# MIA_Array.net
KiCad netlist of a schematic drawn in EAGLE
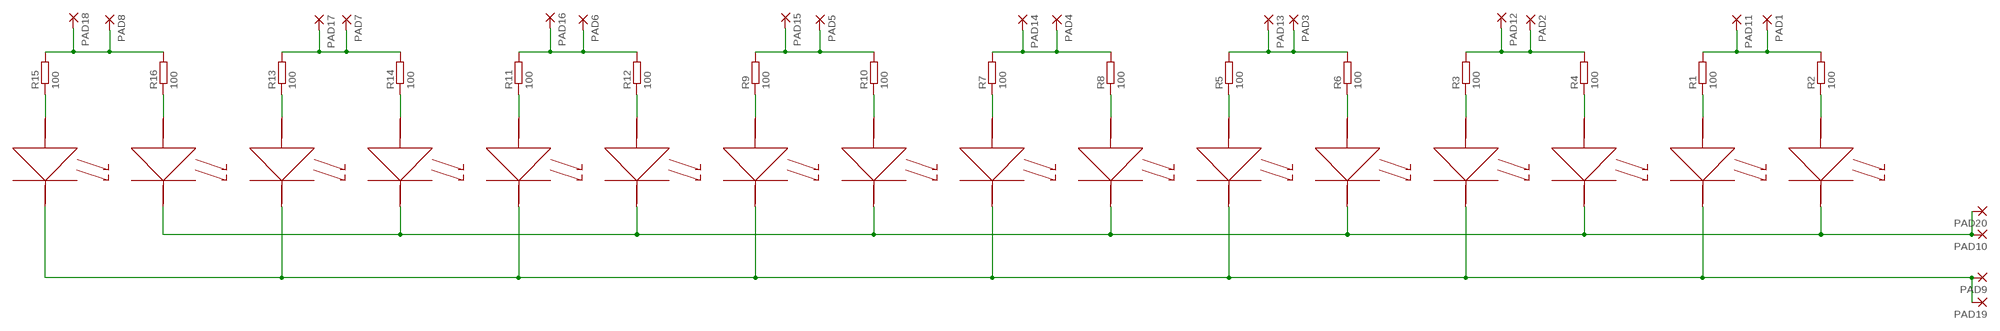
[diagram p0: schematic, sheet 1]

(export (version "E")
  (design (tool "Eeschema 10.0.6"))
  (components
    (comp (ref "PAD1")
      (value "2,54/1,1")
      (footprint "eagle-import:2,54_1,1")
      (libsource (lib "eagle-import") (part "2,54/1,1"))
    )
    (comp (ref "PAD2")
      (value "2,54/1,1")
      (footprint "eagle-import:2,54_1,1")
      (libsource (lib "eagle-import") (part "2,54/1,1"))
    )
    (comp (ref "PAD3")
      (value "2,54/1,1")
      (footprint "eagle-import:2,54_1,1")
      (libsource (lib "eagle-import") (part "2,54/1,1"))
    )
    (comp (ref "PAD4")
      (value "2,54/1,1")
      (footprint "eagle-import:2,54_1,1")
      (libsource (lib "eagle-import") (part "2,54/1,1"))
    )
    (comp (ref "PAD5")
      (value "2,54/1,1")
      (footprint "eagle-import:2,54_1,1")
      (libsource (lib "eagle-import") (part "2,54/1,1"))
    )
    (comp (ref "PAD6")
      (value "2,54/1,1")
      (footprint "eagle-import:2,54_1,1")
      (libsource (lib "eagle-import") (part "2,54/1,1"))
    )
    (comp (ref "PAD7")
      (value "2,54/1,1")
      (footprint "eagle-import:2,54_1,1")
      (libsource (lib "eagle-import") (part "2,54/1,1"))
    )
    (comp (ref "PAD8")
      (value "2,54/1,1")
      (footprint "eagle-import:2,54_1,1")
      (libsource (lib "eagle-import") (part "2,54/1,1"))
    )
    (comp (ref "PAD9")
      (value "2,54/1,1")
      (footprint "eagle-import:2,54_1,1")
      (libsource (lib "eagle-import") (part "2,54/1,1"))
    )
    (comp (ref "PAD10")
      (value "2,54/1,1")
      (footprint "eagle-import:2,54_1,1")
      (libsource (lib "eagle-import") (part "2,54/1,1"))
    )
    (comp (ref "PAD11")
      (value "2,54/1,1")
      (footprint "eagle-import:2,54_1,1")
      (libsource (lib "eagle-import") (part "2,54/1,1"))
    )
    (comp (ref "PAD12")
      (value "2,54/1,1")
      (footprint "eagle-import:2,54_1,1")
      (libsource (lib "eagle-import") (part "2,54/1,1"))
    )
    (comp (ref "PAD13")
      (value "2,54/1,1")
      (footprint "eagle-import:2,54_1,1")
      (libsource (lib "eagle-import") (part "2,54/1,1"))
    )
    (comp (ref "PAD14")
      (value "2,54/1,1")
      (footprint "eagle-import:2,54_1,1")
      (libsource (lib "eagle-import") (part "2,54/1,1"))
    )
    (comp (ref "PAD15")
      (value "2,54/1,1")
      (footprint "eagle-import:2,54_1,1")
      (libsource (lib "eagle-import") (part "2,54/1,1"))
    )
    (comp (ref "PAD16")
      (value "2,54/1,1")
      (footprint "eagle-import:2,54_1,1")
      (libsource (lib "eagle-import") (part "2,54/1,1"))
    )
    (comp (ref "PAD17")
      (value "2,54/1,1")
      (footprint "eagle-import:2,54_1,1")
      (libsource (lib "eagle-import") (part "2,54/1,1"))
    )
    (comp (ref "PAD18")
      (value "2,54/1,1")
      (footprint "eagle-import:2,54_1,1")
      (libsource (lib "eagle-import") (part "2,54/1,1"))
    )
    (comp (ref "PAD19")
      (value "2,54/1,1")
      (footprint "eagle-import:2,54_1,1")
      (libsource (lib "eagle-import") (part "2,54/1,1"))
    )
    (comp (ref "PAD20")
      (value "2,54/1,1")
      (footprint "eagle-import:2,54_1,1")
      (libsource (lib "eagle-import") (part "2,54/1,1"))
    )
    (comp (ref "R1")
      (value "100")
      (footprint "eagle-import:0411_15")
      (libsource (lib "eagle-import") (part "R-EU_0411/15"))
    )
    (comp (ref "R2")
      (value "100")
      (footprint "eagle-import:0411_15")
      (libsource (lib "eagle-import") (part "R-EU_0411/15"))
    )
    (comp (ref "R3")
      (value "100")
      (footprint "eagle-import:0411_15")
      (libsource (lib "eagle-import") (part "R-EU_0411/15"))
    )
    (comp (ref "R4")
      (value "100")
      (footprint "eagle-import:0411_15")
      (libsource (lib "eagle-import") (part "R-EU_0411/15"))
    )
    (comp (ref "R5")
      (value "100")
      (footprint "eagle-import:0411_15")
      (libsource (lib "eagle-import") (part "R-EU_0411/15"))
    )
    (comp (ref "R6")
      (value "100")
      (footprint "eagle-import:0411_15")
      (libsource (lib "eagle-import") (part "R-EU_0411/15"))
    )
    (comp (ref "R7")
      (value "100")
      (footprint "eagle-import:0411_15")
      (libsource (lib "eagle-import") (part "R-EU_0411/15"))
    )
    (comp (ref "R8")
      (value "100")
      (footprint "eagle-import:0411_15")
      (libsource (lib "eagle-import") (part "R-EU_0411/15"))
    )
    (comp (ref "R9")
      (value "100")
      (footprint "eagle-import:0411_15")
      (libsource (lib "eagle-import") (part "R-EU_0411/15"))
    )
    (comp (ref "R10")
      (value "100")
      (footprint "eagle-import:0411_15")
      (libsource (lib "eagle-import") (part "R-EU_0411/15"))
    )
    (comp (ref "R11")
      (value "100")
      (footprint "eagle-import:0411_15")
      (libsource (lib "eagle-import") (part "R-EU_0411/15"))
    )
    (comp (ref "R12")
      (value "100")
      (footprint "eagle-import:0411_15")
      (libsource (lib "eagle-import") (part "R-EU_0411/15"))
    )
    (comp (ref "R13")
      (value "100")
      (footprint "eagle-import:0411_15")
      (libsource (lib "eagle-import") (part "R-EU_0411/15"))
    )
    (comp (ref "R14")
      (value "100")
      (footprint "eagle-import:0411_15")
      (libsource (lib "eagle-import") (part "R-EU_0411/15"))
    )
    (comp (ref "R15")
      (value "100")
      (footprint "eagle-import:0411_15")
      (libsource (lib "eagle-import") (part "R-EU_0411/15"))
    )
    (comp (ref "R16")
      (value "100")
      (footprint "eagle-import:0411_15")
      (libsource (lib "eagle-import") (part "R-EU_0411/15"))
    )
    (comp (ref "U$1")
      (value "L150-3080502400000")
      (footprint "eagle-import:SMD-5050")
      (libsource (lib "eagle-import") (part "L150-3080502400000"))
    )
    (comp (ref "U$2")
      (value "L150-3080502400000")
      (footprint "eagle-import:SMD-5050")
      (libsource (lib "eagle-import") (part "L150-3080502400000"))
    )
    (comp (ref "U$3")
      (value "L150-3080502400000")
      (footprint "eagle-import:SMD-5050")
      (libsource (lib "eagle-import") (part "L150-3080502400000"))
    )
    (comp (ref "U$4")
      (value "L150-3080502400000")
      (footprint "eagle-import:SMD-5050")
      (libsource (lib "eagle-import") (part "L150-3080502400000"))
    )
    (comp (ref "U$5")
      (value "L150-3080502400000")
      (footprint "eagle-import:SMD-5050")
      (libsource (lib "eagle-import") (part "L150-3080502400000"))
    )
    (comp (ref "U$6")
      (value "L150-3080502400000")
      (footprint "eagle-import:SMD-5050")
      (libsource (lib "eagle-import") (part "L150-3080502400000"))
    )
    (comp (ref "U$7")
      (value "L150-3080502400000")
      (footprint "eagle-import:SMD-5050")
      (libsource (lib "eagle-import") (part "L150-3080502400000"))
    )
    (comp (ref "U$8")
      (value "L150-3080502400000")
      (footprint "eagle-import:SMD-5050")
      (libsource (lib "eagle-import") (part "L150-3080502400000"))
    )
    (comp (ref "U$9")
      (value "L150-3080502400000")
      (footprint "eagle-import:SMD-5050")
      (libsource (lib "eagle-import") (part "L150-3080502400000"))
    )
    (comp (ref "U$10")
      (value "L150-3080502400000")
      (footprint "eagle-import:SMD-5050")
      (libsource (lib "eagle-import") (part "L150-3080502400000"))
    )
    (comp (ref "U$11")
      (value "L150-3080502400000")
      (footprint "eagle-import:SMD-5050")
      (libsource (lib "eagle-import") (part "L150-3080502400000"))
    )
    (comp (ref "U$12")
      (value "L150-3080502400000")
      (footprint "eagle-import:SMD-5050")
      (libsource (lib "eagle-import") (part "L150-3080502400000"))
    )
    (comp (ref "U$13")
      (value "L150-3080502400000")
      (footprint "eagle-import:SMD-5050")
      (libsource (lib "eagle-import") (part "L150-3080502400000"))
    )
    (comp (ref "U$14")
      (value "L150-3080502400000")
      (footprint "eagle-import:SMD-5050")
      (libsource (lib "eagle-import") (part "L150-3080502400000"))
    )
    (comp (ref "U$15")
      (value "L150-3080502400000")
      (footprint "eagle-import:SMD-5050")
      (libsource (lib "eagle-import") (part "L150-3080502400000"))
    )
    (comp (ref "U$16")
      (value "L150-3080502400000")
      (footprint "eagle-import:SMD-5050")
      (libsource (lib "eagle-import") (part "L150-3080502400000"))
    )
  )
  (nets
    (net (code "1") (name "Net-(PAD1-P)") (class "Default")
      (node (ref "PAD1") (pin "1") (pinfunction "P_1") (pintype "passive"))
      (node (ref "PAD11") (pin "1") (pinfunction "P_1") (pintype "passive"))
      (node (ref "R1") (pin "2") (pinfunction "2_2") (pintype "passive"))
      (node (ref "R2") (pin "2") (pinfunction "2_2") (pintype "passive"))
    )
    (net (code "2") (name "Net-(PAD10-P)") (class "Default")
      (node (ref "PAD10") (pin "1") (pinfunction "P_1") (pintype "passive"))
      (node (ref "PAD20") (pin "1") (pinfunction "P_1") (pintype "passive"))
      (node (ref "U$11") (pin "CA") (pinfunction "CA_CA") (pintype "bidirectional"))
      (node (ref "U$11") (pin "CA2") (pinfunction "CA_CA2") (pintype "bidirectional"))
      (node (ref "U$12") (pin "CA") (pinfunction "CA_CA") (pintype "bidirectional"))
      (node (ref "U$12") (pin "CA2") (pinfunction "CA_CA2") (pintype "bidirectional"))
      (node (ref "U$14") (pin "CA") (pinfunction "CA_CA") (pintype "bidirectional"))
      (node (ref "U$14") (pin "CA2") (pinfunction "CA_CA2") (pintype "bidirectional"))
      (node (ref "U$16") (pin "CA") (pinfunction "CA_CA") (pintype "bidirectional"))
      (node (ref "U$16") (pin "CA2") (pinfunction "CA_CA2") (pintype "bidirectional"))
      (node (ref "U$2") (pin "CA") (pinfunction "CA_CA") (pintype "bidirectional"))
      (node (ref "U$2") (pin "CA2") (pinfunction "CA_CA2") (pintype "bidirectional"))
      (node (ref "U$5") (pin "CA") (pinfunction "CA_CA") (pintype "bidirectional"))
      (node (ref "U$5") (pin "CA2") (pinfunction "CA_CA2") (pintype "bidirectional"))
      (node (ref "U$7") (pin "CA") (pinfunction "CA_CA") (pintype "bidirectional"))
      (node (ref "U$7") (pin "CA2") (pinfunction "CA_CA2") (pintype "bidirectional"))
      (node (ref "U$9") (pin "CA") (pinfunction "CA_CA") (pintype "bidirectional"))
      (node (ref "U$9") (pin "CA2") (pinfunction "CA_CA2") (pintype "bidirectional"))
    )
    (net (code "3") (name "Net-(PAD12-P)") (class "Default")
      (node (ref "PAD12") (pin "1") (pinfunction "P_1") (pintype "passive"))
      (node (ref "PAD2") (pin "1") (pinfunction "P_1") (pintype "passive"))
      (node (ref "R3") (pin "2") (pinfunction "2_2") (pintype "passive"))
      (node (ref "R4") (pin "2") (pinfunction "2_2") (pintype "passive"))
    )
    (net (code "4") (name "Net-(PAD13-P)") (class "Default")
      (node (ref "PAD13") (pin "1") (pinfunction "P_1") (pintype "passive"))
      (node (ref "PAD3") (pin "1") (pinfunction "P_1") (pintype "passive"))
      (node (ref "R5") (pin "2") (pinfunction "2_2") (pintype "passive"))
      (node (ref "R6") (pin "2") (pinfunction "2_2") (pintype "passive"))
    )
    (net (code "5") (name "Net-(PAD14-P)") (class "Default")
      (node (ref "PAD14") (pin "1") (pinfunction "P_1") (pintype "passive"))
      (node (ref "PAD4") (pin "1") (pinfunction "P_1") (pintype "passive"))
      (node (ref "R7") (pin "2") (pinfunction "2_2") (pintype "passive"))
      (node (ref "R8") (pin "2") (pinfunction "2_2") (pintype "passive"))
    )
    (net (code "6") (name "Net-(PAD15-P)") (class "Default")
      (node (ref "PAD15") (pin "1") (pinfunction "P_1") (pintype "passive"))
      (node (ref "PAD5") (pin "1") (pinfunction "P_1") (pintype "passive"))
      (node (ref "R10") (pin "2") (pinfunction "2_2") (pintype "passive"))
      (node (ref "R9") (pin "2") (pinfunction "2_2") (pintype "passive"))
    )
    (net (code "7") (name "Net-(PAD16-P)") (class "Default")
      (node (ref "PAD16") (pin "1") (pinfunction "P_1") (pintype "passive"))
      (node (ref "PAD6") (pin "1") (pinfunction "P_1") (pintype "passive"))
      (node (ref "R11") (pin "2") (pinfunction "2_2") (pintype "passive"))
      (node (ref "R12") (pin "2") (pinfunction "2_2") (pintype "passive"))
    )
    (net (code "8") (name "Net-(PAD17-P)") (class "Default")
      (node (ref "PAD17") (pin "1") (pinfunction "P_1") (pintype "passive"))
      (node (ref "PAD7") (pin "1") (pinfunction "P_1") (pintype "passive"))
      (node (ref "R13") (pin "2") (pinfunction "2_2") (pintype "passive"))
      (node (ref "R14") (pin "2") (pinfunction "2_2") (pintype "passive"))
    )
    (net (code "9") (name "Net-(PAD18-P)") (class "Default")
      (node (ref "PAD18") (pin "1") (pinfunction "P_1") (pintype "passive"))
      (node (ref "PAD8") (pin "1") (pinfunction "P_1") (pintype "passive"))
      (node (ref "R15") (pin "2") (pinfunction "2_2") (pintype "passive"))
      (node (ref "R16") (pin "2") (pinfunction "2_2") (pintype "passive"))
    )
    (net (code "10") (name "Net-(PAD19-P)") (class "Default")
      (node (ref "PAD19") (pin "1") (pinfunction "P_1") (pintype "passive"))
      (node (ref "PAD9") (pin "1") (pinfunction "P_1") (pintype "passive"))
      (node (ref "U$1") (pin "CA") (pinfunction "CA_CA") (pintype "bidirectional"))
      (node (ref "U$1") (pin "CA2") (pinfunction "CA_CA2") (pintype "bidirectional"))
      (node (ref "U$10") (pin "CA") (pinfunction "CA_CA") (pintype "bidirectional"))
      (node (ref "U$10") (pin "CA2") (pinfunction "CA_CA2") (pintype "bidirectional"))
      (node (ref "U$13") (pin "CA") (pinfunction "CA_CA") (pintype "bidirectional"))
      (node (ref "U$13") (pin "CA2") (pinfunction "CA_CA2") (pintype "bidirectional"))
      (node (ref "U$15") (pin "CA") (pinfunction "CA_CA") (pintype "bidirectional"))
      (node (ref "U$15") (pin "CA2") (pinfunction "CA_CA2") (pintype "bidirectional"))
      (node (ref "U$3") (pin "CA") (pinfunction "CA_CA") (pintype "bidirectional"))
      (node (ref "U$3") (pin "CA2") (pinfunction "CA_CA2") (pintype "bidirectional"))
      (node (ref "U$4") (pin "CA") (pinfunction "CA_CA") (pintype "bidirectional"))
      (node (ref "U$4") (pin "CA2") (pinfunction "CA_CA2") (pintype "bidirectional"))
      (node (ref "U$6") (pin "CA") (pinfunction "CA_CA") (pintype "bidirectional"))
      (node (ref "U$6") (pin "CA2") (pinfunction "CA_CA2") (pintype "bidirectional"))
      (node (ref "U$8") (pin "CA") (pinfunction "CA_CA") (pintype "bidirectional"))
      (node (ref "U$8") (pin "CA2") (pinfunction "CA_CA2") (pintype "bidirectional"))
    )
    (net (code "11") (name "Net-(R1-Pad1)") (class "Default")
      (node (ref "R1") (pin "1") (pinfunction "1_1") (pintype "passive"))
      (node (ref "U$4") (pin "AN") (pinfunction "AN_AN") (pintype "bidirectional"))
      (node (ref "U$4") (pin "AN2") (pinfunction "AN_AN2") (pintype "bidirectional"))
    )
    (net (code "12") (name "Net-(R2-Pad1)") (class "Default")
      (node (ref "R2") (pin "1") (pinfunction "1_1") (pintype "passive"))
      (node (ref "U$12") (pin "AN") (pinfunction "AN_AN") (pintype "bidirectional"))
      (node (ref "U$12") (pin "AN2") (pinfunction "AN_AN2") (pintype "bidirectional"))
    )
    (net (code "13") (name "Net-(R3-Pad1)") (class "Default")
      (node (ref "R3") (pin "1") (pinfunction "1_1") (pintype "passive"))
      (node (ref "U$1") (pin "AN") (pinfunction "AN_AN") (pintype "bidirectional"))
      (node (ref "U$1") (pin "AN2") (pinfunction "AN_AN2") (pintype "bidirectional"))
    )
    (net (code "14") (name "Net-(R4-Pad1)") (class "Default")
      (node (ref "R4") (pin "1") (pinfunction "1_1") (pintype "passive"))
      (node (ref "U$2") (pin "AN") (pinfunction "AN_AN") (pintype "bidirectional"))
      (node (ref "U$2") (pin "AN2") (pinfunction "AN_AN2") (pintype "bidirectional"))
    )
    (net (code "15") (name "Net-(R5-Pad1)") (class "Default")
      (node (ref "R5") (pin "1") (pinfunction "1_1") (pintype "passive"))
      (node (ref "U$3") (pin "AN") (pinfunction "AN_AN") (pintype "bidirectional"))
      (node (ref "U$3") (pin "AN2") (pinfunction "AN_AN2") (pintype "bidirectional"))
    )
    (net (code "16") (name "Net-(R6-Pad1)") (class "Default")
      (node (ref "R6") (pin "1") (pinfunction "1_1") (pintype "passive"))
      (node (ref "U$5") (pin "AN") (pinfunction "AN_AN") (pintype "bidirectional"))
      (node (ref "U$5") (pin "AN2") (pinfunction "AN_AN2") (pintype "bidirectional"))
    )
    (net (code "17") (name "Net-(R7-Pad1)") (class "Default")
      (node (ref "R7") (pin "1") (pinfunction "1_1") (pintype "passive"))
      (node (ref "U$6") (pin "AN") (pinfunction "AN_AN") (pintype "bidirectional"))
      (node (ref "U$6") (pin "AN2") (pinfunction "AN_AN2") (pintype "bidirectional"))
    )
    (net (code "18") (name "Net-(R8-Pad1)") (class "Default")
      (node (ref "R8") (pin "1") (pinfunction "1_1") (pintype "passive"))
      (node (ref "U$7") (pin "AN") (pinfunction "AN_AN") (pintype "bidirectional"))
      (node (ref "U$7") (pin "AN2") (pinfunction "AN_AN2") (pintype "bidirectional"))
    )
    (net (code "19") (name "Net-(R9-Pad1)") (class "Default")
      (node (ref "R9") (pin "1") (pinfunction "1_1") (pintype "passive"))
      (node (ref "U$8") (pin "AN") (pinfunction "AN_AN") (pintype "bidirectional"))
      (node (ref "U$8") (pin "AN2") (pinfunction "AN_AN2") (pintype "bidirectional"))
    )
    (net (code "20") (name "Net-(R10-Pad1)") (class "Default")
      (node (ref "R10") (pin "1") (pinfunction "1_1") (pintype "passive"))
      (node (ref "U$9") (pin "AN") (pinfunction "AN_AN") (pintype "bidirectional"))
      (node (ref "U$9") (pin "AN2") (pinfunction "AN_AN2") (pintype "bidirectional"))
    )
    (net (code "21") (name "Net-(R11-Pad1)") (class "Default")
      (node (ref "R11") (pin "1") (pinfunction "1_1") (pintype "passive"))
      (node (ref "U$10") (pin "AN") (pinfunction "AN_AN") (pintype "bidirectional"))
      (node (ref "U$10") (pin "AN2") (pinfunction "AN_AN2") (pintype "bidirectional"))
    )
    (net (code "22") (name "Net-(R12-Pad1)") (class "Default")
      (node (ref "R12") (pin "1") (pinfunction "1_1") (pintype "passive"))
      (node (ref "U$11") (pin "AN") (pinfunction "AN_AN") (pintype "bidirectional"))
      (node (ref "U$11") (pin "AN2") (pinfunction "AN_AN2") (pintype "bidirectional"))
    )
    (net (code "23") (name "Net-(R13-Pad1)") (class "Default")
      (node (ref "R13") (pin "1") (pinfunction "1_1") (pintype "passive"))
      (node (ref "U$13") (pin "AN") (pinfunction "AN_AN") (pintype "bidirectional"))
      (node (ref "U$13") (pin "AN2") (pinfunction "AN_AN2") (pintype "bidirectional"))
    )
    (net (code "24") (name "Net-(R14-Pad1)") (class "Default")
      (node (ref "R14") (pin "1") (pinfunction "1_1") (pintype "passive"))
      (node (ref "U$14") (pin "AN") (pinfunction "AN_AN") (pintype "bidirectional"))
      (node (ref "U$14") (pin "AN2") (pinfunction "AN_AN2") (pintype "bidirectional"))
    )
    (net (code "25") (name "Net-(R15-Pad1)") (class "Default")
      (node (ref "R15") (pin "1") (pinfunction "1_1") (pintype "passive"))
      (node (ref "U$15") (pin "AN") (pinfunction "AN_AN") (pintype "bidirectional"))
      (node (ref "U$15") (pin "AN2") (pinfunction "AN_AN2") (pintype "bidirectional"))
    )
    (net (code "26") (name "Net-(R16-Pad1)") (class "Default")
      (node (ref "R16") (pin "1") (pinfunction "1_1") (pintype "passive"))
      (node (ref "U$16") (pin "AN") (pinfunction "AN_AN") (pintype "bidirectional"))
      (node (ref "U$16") (pin "AN2") (pinfunction "AN_AN2") (pintype "bidirectional"))
    )
  )
)
